# ADC_Board_Right.net
KiCad netlist of a schematic drawn in EAGLE
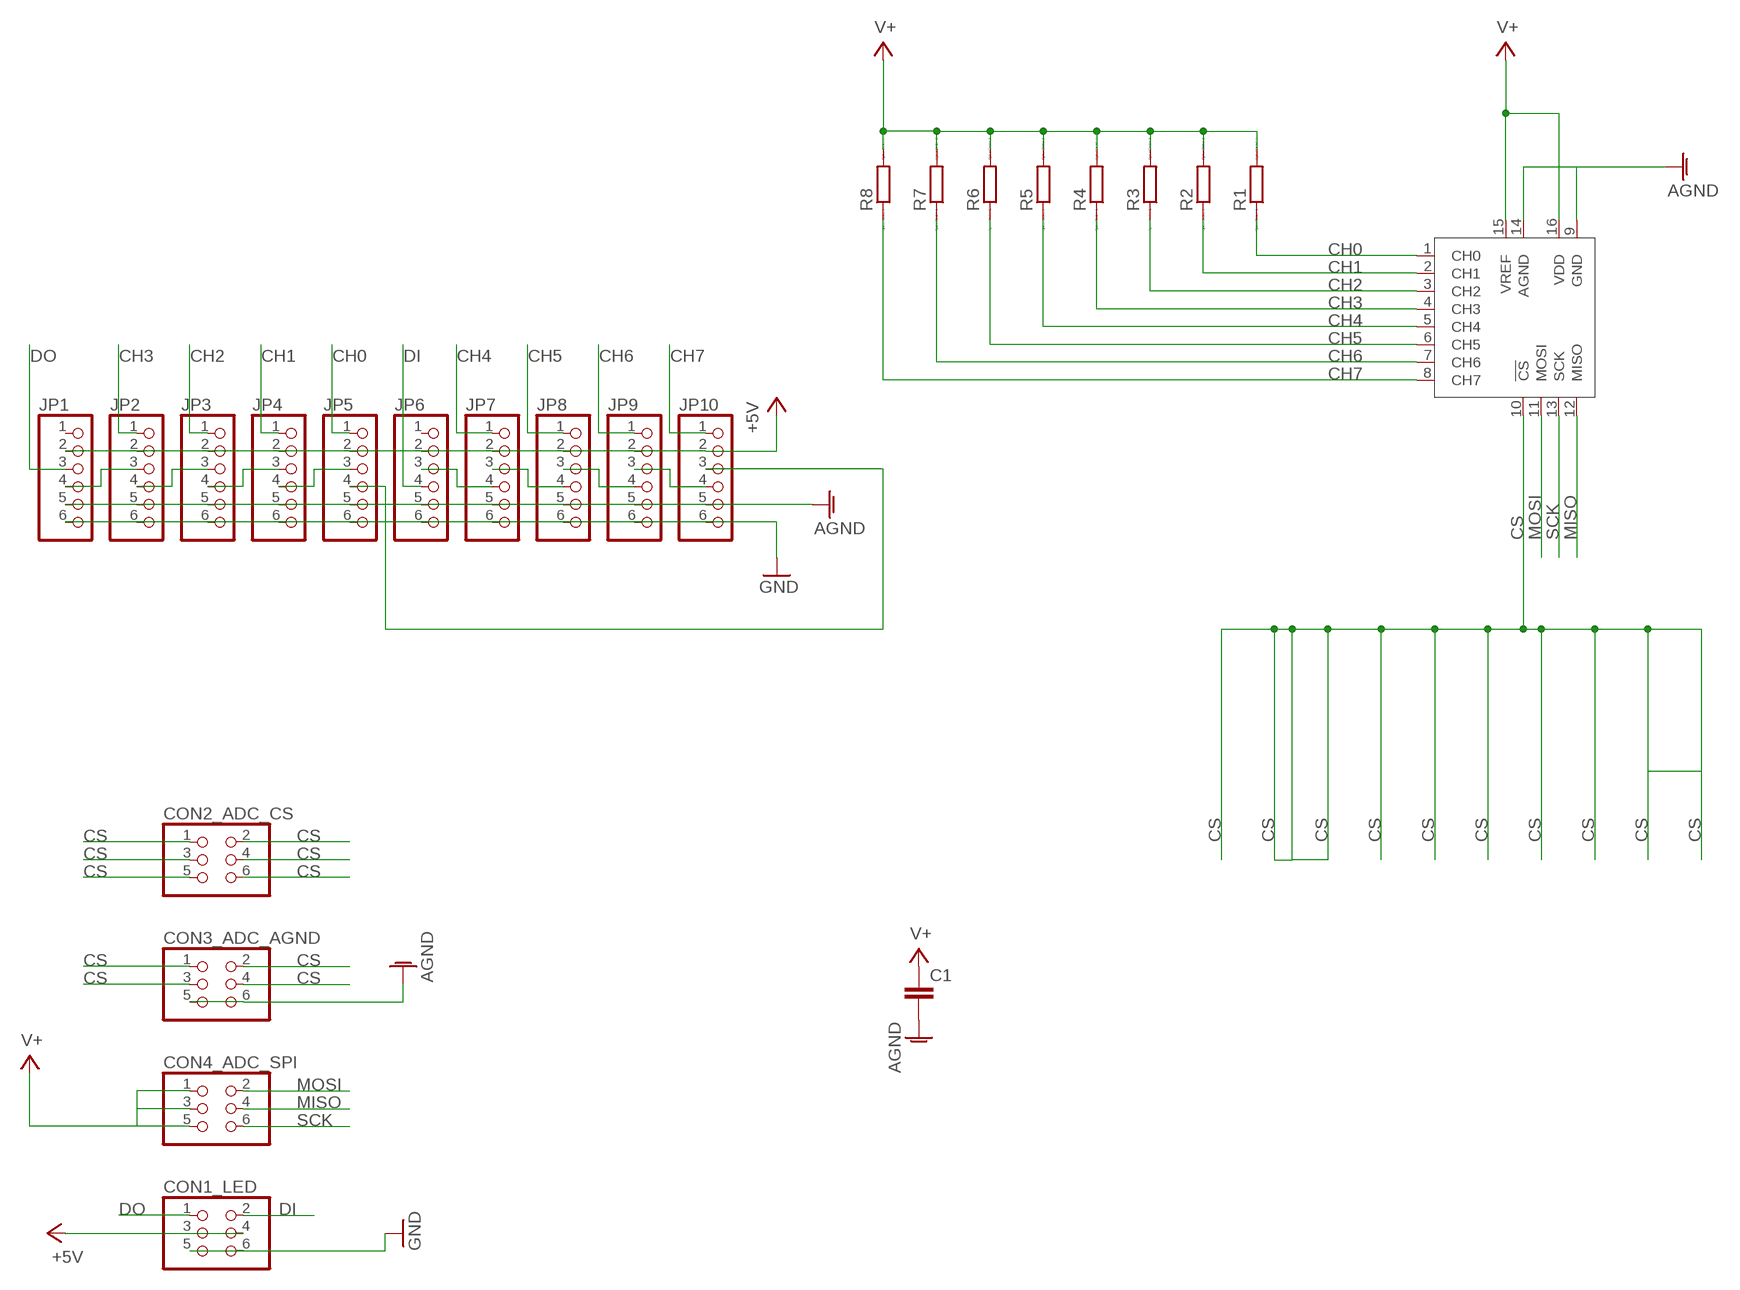
[diagram p0: schematic, sheet 1]

(export (version "E")
  (design (tool "Eeschema 10.0.6"))
  (components
    (comp (ref "C1")
      (value "C-EU050-025X075")
      (footprint "eagle-import:C050-025X075")
      (libsource (lib "eagle-import") (part "C-EU050-025X075"))
    )
    (comp (ref "CON1_LED")
      (value "PINHD-2X3")
      (footprint "eagle-import:2X03")
      (libsource (lib "eagle-import") (part "PINHD-2X3"))
    )
    (comp (ref "CON2_ADC_CS")
      (value "PINHD-2X3")
      (footprint "eagle-import:2X03")
      (libsource (lib "eagle-import") (part "PINHD-2X3"))
    )
    (comp (ref "CON3_ADC_AGND")
      (value "PINHD-2X3")
      (footprint "eagle-import:2X03")
      (libsource (lib "eagle-import") (part "PINHD-2X3"))
    )
    (comp (ref "CON4_ADC_SPI")
      (value "PINHD-2X3")
      (footprint "eagle-import:2X03")
      (libsource (lib "eagle-import") (part "PINHD-2X3"))
    )
    (comp (ref "JP1")
      (value "PINHD-1X6")
      (footprint "eagle-import:1X06")
      (libsource (lib "eagle-import") (part "PINHD-1X6"))
    )
    (comp (ref "JP2")
      (value "PINHD-1X6")
      (footprint "eagle-import:1X06")
      (libsource (lib "eagle-import") (part "PINHD-1X6"))
    )
    (comp (ref "JP3")
      (value "PINHD-1X6")
      (footprint "eagle-import:1X06")
      (libsource (lib "eagle-import") (part "PINHD-1X6"))
    )
    (comp (ref "JP4")
      (value "PINHD-1X6")
      (footprint "eagle-import:1X06")
      (libsource (lib "eagle-import") (part "PINHD-1X6"))
    )
    (comp (ref "JP5")
      (value "PINHD-1X6")
      (footprint "eagle-import:1X06")
      (libsource (lib "eagle-import") (part "PINHD-1X6"))
    )
    (comp (ref "JP6")
      (value "PINHD-1X6")
      (footprint "eagle-import:1X06")
      (libsource (lib "eagle-import") (part "PINHD-1X6"))
    )
    (comp (ref "JP7")
      (value "PINHD-1X6")
      (footprint "eagle-import:1X06")
      (libsource (lib "eagle-import") (part "PINHD-1X6"))
    )
    (comp (ref "JP8")
      (value "PINHD-1X6")
      (footprint "eagle-import:1X06")
      (libsource (lib "eagle-import") (part "PINHD-1X6"))
    )
    (comp (ref "JP9")
      (value "PINHD-1X6")
      (footprint "eagle-import:1X06")
      (libsource (lib "eagle-import") (part "PINHD-1X6"))
    )
    (comp (ref "JP10")
      (value "PINHD-1X6")
      (footprint "eagle-import:1X06")
      (libsource (lib "eagle-import") (part "PINHD-1X6"))
    )
    (comp (ref "R1")
      (value "R-EU_0617_22")
      (footprint "eagle-import:0617_22")
      (libsource (lib "eagle-import") (part "R-EU_0617_22"))
    )
    (comp (ref "R2")
      (value "R-EU_0617_22")
      (footprint "eagle-import:0617_22")
      (libsource (lib "eagle-import") (part "R-EU_0617_22"))
    )
    (comp (ref "R3")
      (value "R-EU_0617_22")
      (footprint "eagle-import:0617_22")
      (libsource (lib "eagle-import") (part "R-EU_0617_22"))
    )
    (comp (ref "R4")
      (value "R-EU_0617_22")
      (footprint "eagle-import:0617_22")
      (libsource (lib "eagle-import") (part "R-EU_0617_22"))
    )
    (comp (ref "R5")
      (value "R-EU_0617_22")
      (footprint "eagle-import:0617_22")
      (libsource (lib "eagle-import") (part "R-EU_0617_22"))
    )
    (comp (ref "R6")
      (value "R-EU_0617_22")
      (footprint "eagle-import:0617_22")
      (libsource (lib "eagle-import") (part "R-EU_0617_22"))
    )
    (comp (ref "R7")
      (value "R-EU_0617_22")
      (footprint "eagle-import:0617_22")
      (libsource (lib "eagle-import") (part "R-EU_0617_22"))
    )
    (comp (ref "R8")
      (value "R-EU_0617_22")
      (footprint "eagle-import:0617_22")
      (libsource (lib "eagle-import") (part "R-EU_0617_22"))
    )
    (comp (ref "U$1")
      (value "MCP3008P")
      (footprint "eagle-import:DIL16")
      (libsource (lib "eagle-import") (part "MCP3008P"))
    )
  )
  (nets
    (net (code "1") (name "+5V") (class "Default")
      (node (ref "CON1_LED") (pin "3") (pinfunction "3_3") (pintype "passive"))
      (node (ref "CON1_LED") (pin "4") (pinfunction "4_4") (pintype "passive"))
      (node (ref "JP1") (pin "2") (pinfunction "2_2") (pintype "passive"))
      (node (ref "JP10") (pin "2") (pinfunction "2_2") (pintype "passive"))
      (node (ref "JP2") (pin "2") (pinfunction "2_2") (pintype "passive"))
      (node (ref "JP3") (pin "2") (pinfunction "2_2") (pintype "passive"))
      (node (ref "JP4") (pin "2") (pinfunction "2_2") (pintype "passive"))
      (node (ref "JP5") (pin "2") (pinfunction "2_2") (pintype "passive"))
      (node (ref "JP6") (pin "2") (pinfunction "2_2") (pintype "passive"))
      (node (ref "JP7") (pin "2") (pinfunction "2_2") (pintype "passive"))
      (node (ref "JP8") (pin "2") (pinfunction "2_2") (pintype "passive"))
      (node (ref "JP9") (pin "2") (pinfunction "2_2") (pintype "passive"))
    )
    (net (code "2") (name "/CH0") (class "Default")
      (node (ref "JP5") (pin "1") (pinfunction "1_1") (pintype "passive"))
      (node (ref "R1") (pin "1") (pinfunction "1_1") (pintype "passive"))
      (node (ref "U$1") (pin "1") (pinfunction "CH0_1") (pintype "input"))
    )
    (net (code "3") (name "/CH1") (class "Default")
      (node (ref "JP4") (pin "1") (pinfunction "1_1") (pintype "passive"))
      (node (ref "R2") (pin "1") (pinfunction "1_1") (pintype "passive"))
      (node (ref "U$1") (pin "2") (pinfunction "CH1_2") (pintype "input"))
    )
    (net (code "4") (name "/CH2") (class "Default")
      (node (ref "JP3") (pin "1") (pinfunction "1_1") (pintype "passive"))
      (node (ref "R3") (pin "1") (pinfunction "1_1") (pintype "passive"))
      (node (ref "U$1") (pin "3") (pinfunction "CH2_3") (pintype "input"))
    )
    (net (code "5") (name "/CH3") (class "Default")
      (node (ref "JP2") (pin "1") (pinfunction "1_1") (pintype "passive"))
      (node (ref "R4") (pin "1") (pinfunction "1_1") (pintype "passive"))
      (node (ref "U$1") (pin "4") (pinfunction "CH3_4") (pintype "input"))
    )
    (net (code "6") (name "/CH4") (class "Default")
      (node (ref "JP7") (pin "1") (pinfunction "1_1") (pintype "passive"))
      (node (ref "R5") (pin "1") (pinfunction "1_1") (pintype "passive"))
      (node (ref "U$1") (pin "5") (pinfunction "CH4_5") (pintype "input"))
    )
    (net (code "7") (name "/CH5") (class "Default")
      (node (ref "JP8") (pin "1") (pinfunction "1_1") (pintype "passive"))
      (node (ref "R6") (pin "1") (pinfunction "1_1") (pintype "passive"))
      (node (ref "U$1") (pin "6") (pinfunction "CH5_6") (pintype "input"))
    )
    (net (code "8") (name "/CH6") (class "Default")
      (node (ref "JP9") (pin "1") (pinfunction "1_1") (pintype "passive"))
      (node (ref "R7") (pin "1") (pinfunction "1_1") (pintype "passive"))
      (node (ref "U$1") (pin "7") (pinfunction "CH6_7") (pintype "input"))
    )
    (net (code "9") (name "/CH7") (class "Default")
      (node (ref "JP10") (pin "1") (pinfunction "1_1") (pintype "passive"))
      (node (ref "R8") (pin "1") (pinfunction "1_1") (pintype "passive"))
      (node (ref "U$1") (pin "8") (pinfunction "CH7_8") (pintype "input"))
    )
    (net (code "10") (name "/CS") (class "Default")
      (node (ref "CON2_ADC_CS") (pin "1") (pinfunction "1_1") (pintype "passive"))
      (node (ref "CON2_ADC_CS") (pin "2") (pinfunction "2_2") (pintype "passive"))
      (node (ref "CON2_ADC_CS") (pin "3") (pinfunction "3_3") (pintype "passive"))
      (node (ref "CON2_ADC_CS") (pin "4") (pinfunction "4_4") (pintype "passive"))
      (node (ref "CON2_ADC_CS") (pin "5") (pinfunction "5_5") (pintype "passive"))
      (node (ref "CON2_ADC_CS") (pin "6") (pinfunction "6_6") (pintype "passive"))
      (node (ref "CON3_ADC_AGND") (pin "1") (pinfunction "1_1") (pintype "passive"))
      (node (ref "CON3_ADC_AGND") (pin "2") (pinfunction "2_2") (pintype "passive"))
      (node (ref "CON3_ADC_AGND") (pin "3") (pinfunction "3_3") (pintype "passive"))
      (node (ref "CON3_ADC_AGND") (pin "4") (pinfunction "4_4") (pintype "passive"))
      (node (ref "U$1") (pin "10") (pinfunction "~{CS}_10") (pintype "input"))
    )
    (net (code "11") (name "/DI") (class "Default")
      (node (ref "CON1_LED") (pin "2") (pinfunction "2_2") (pintype "passive"))
      (node (ref "JP6") (pin "4") (pinfunction "4_4") (pintype "passive"))
    )
    (net (code "12") (name "/DO") (class "Default")
      (node (ref "CON1_LED") (pin "1") (pinfunction "1_1") (pintype "passive"))
      (node (ref "JP1") (pin "3") (pinfunction "3_3") (pintype "passive"))
    )
    (net (code "13") (name "/MISO") (class "Default")
      (node (ref "CON4_ADC_SPI") (pin "4") (pinfunction "4_4") (pintype "passive"))
      (node (ref "U$1") (pin "12") (pinfunction "MISO_12") (pintype "output"))
    )
    (net (code "14") (name "/MOSI") (class "Default")
      (node (ref "CON4_ADC_SPI") (pin "2") (pinfunction "2_2") (pintype "passive"))
      (node (ref "U$1") (pin "11") (pinfunction "MOSI_11") (pintype "input"))
    )
    (net (code "15") (name "/SCK") (class "Default")
      (node (ref "CON4_ADC_SPI") (pin "6") (pinfunction "6_6") (pintype "passive"))
      (node (ref "U$1") (pin "13") (pinfunction "SCK_13") (pintype "input"))
    )
    (net (code "16") (name "AGND") (class "Default")
      (node (ref "C1") (pin "2") (pinfunction "2_2") (pintype "passive"))
      (node (ref "CON3_ADC_AGND") (pin "5") (pinfunction "5_5") (pintype "passive"))
      (node (ref "CON3_ADC_AGND") (pin "6") (pinfunction "6_6") (pintype "passive"))
      (node (ref "JP1") (pin "5") (pinfunction "5_5") (pintype "passive"))
      (node (ref "JP10") (pin "5") (pinfunction "5_5") (pintype "passive"))
      (node (ref "JP2") (pin "5") (pinfunction "5_5") (pintype "passive"))
      (node (ref "JP3") (pin "5") (pinfunction "5_5") (pintype "passive"))
      (node (ref "JP4") (pin "5") (pinfunction "5_5") (pintype "passive"))
      (node (ref "JP5") (pin "5") (pinfunction "5_5") (pintype "passive"))
      (node (ref "JP6") (pin "5") (pinfunction "5_5") (pintype "passive"))
      (node (ref "JP7") (pin "5") (pinfunction "5_5") (pintype "passive"))
      (node (ref "JP8") (pin "5") (pinfunction "5_5") (pintype "passive"))
      (node (ref "JP9") (pin "5") (pinfunction "5_5") (pintype "passive"))
      (node (ref "U$1") (pin "14") (pinfunction "AGND_14") (pintype "power_in"))
      (node (ref "U$1") (pin "9") (pinfunction "GND_9") (pintype "power_in"))
    )
    (net (code "17") (name "GND") (class "Default")
      (node (ref "CON1_LED") (pin "5") (pinfunction "5_5") (pintype "passive"))
      (node (ref "CON1_LED") (pin "6") (pinfunction "6_6") (pintype "passive"))
      (node (ref "JP1") (pin "6") (pinfunction "6_6") (pintype "passive"))
      (node (ref "JP10") (pin "6") (pinfunction "6_6") (pintype "passive"))
      (node (ref "JP2") (pin "6") (pinfunction "6_6") (pintype "passive"))
      (node (ref "JP3") (pin "6") (pinfunction "6_6") (pintype "passive"))
      (node (ref "JP4") (pin "6") (pinfunction "6_6") (pintype "passive"))
      (node (ref "JP5") (pin "6") (pinfunction "6_6") (pintype "passive"))
      (node (ref "JP6") (pin "6") (pinfunction "6_6") (pintype "passive"))
      (node (ref "JP7") (pin "6") (pinfunction "6_6") (pintype "passive"))
      (node (ref "JP8") (pin "6") (pinfunction "6_6") (pintype "passive"))
      (node (ref "JP9") (pin "6") (pinfunction "6_6") (pintype "passive"))
    )
    (net (code "18") (name "Net-(JP1-Pad4)") (class "Default")
      (node (ref "JP1") (pin "4") (pinfunction "4_4") (pintype "passive"))
      (node (ref "JP2") (pin "3") (pinfunction "3_3") (pintype "passive"))
    )
    (net (code "19") (name "Net-(JP2-Pad4)") (class "Default")
      (node (ref "JP2") (pin "4") (pinfunction "4_4") (pintype "passive"))
      (node (ref "JP3") (pin "3") (pinfunction "3_3") (pintype "passive"))
    )
    (net (code "20") (name "Net-(JP3-Pad4)") (class "Default")
      (node (ref "JP3") (pin "4") (pinfunction "4_4") (pintype "passive"))
      (node (ref "JP4") (pin "3") (pinfunction "3_3") (pintype "passive"))
    )
    (net (code "21") (name "Net-(JP4-Pad4)") (class "Default")
      (node (ref "JP4") (pin "4") (pinfunction "4_4") (pintype "passive"))
      (node (ref "JP5") (pin "3") (pinfunction "3_3") (pintype "passive"))
    )
    (net (code "22") (name "Net-(JP6-Pad3)") (class "Default")
      (node (ref "JP6") (pin "3") (pinfunction "3_3") (pintype "passive"))
      (node (ref "JP7") (pin "4") (pinfunction "4_4") (pintype "passive"))
    )
    (net (code "23") (name "Net-(JP7-Pad3)") (class "Default")
      (node (ref "JP7") (pin "3") (pinfunction "3_3") (pintype "passive"))
      (node (ref "JP8") (pin "4") (pinfunction "4_4") (pintype "passive"))
    )
    (net (code "24") (name "Net-(JP8-Pad3)") (class "Default")
      (node (ref "JP8") (pin "3") (pinfunction "3_3") (pintype "passive"))
      (node (ref "JP9") (pin "4") (pinfunction "4_4") (pintype "passive"))
    )
    (net (code "25") (name "Net-(JP10-Pad3)") (class "Default")
      (node (ref "JP10") (pin "3") (pinfunction "3_3") (pintype "passive"))
      (node (ref "JP5") (pin "4") (pinfunction "4_4") (pintype "passive"))
    )
    (net (code "26") (name "Net-(JP10-Pad4)") (class "Default")
      (node (ref "JP10") (pin "4") (pinfunction "4_4") (pintype "passive"))
      (node (ref "JP9") (pin "3") (pinfunction "3_3") (pintype "passive"))
    )
    (net (code "27") (name "V+") (class "Default")
      (node (ref "C1") (pin "1") (pinfunction "1_1") (pintype "passive"))
      (node (ref "CON4_ADC_SPI") (pin "1") (pinfunction "1_1") (pintype "passive"))
      (node (ref "CON4_ADC_SPI") (pin "3") (pinfunction "3_3") (pintype "passive"))
      (node (ref "CON4_ADC_SPI") (pin "5") (pinfunction "5_5") (pintype "passive"))
      (node (ref "R1") (pin "2") (pinfunction "2_2") (pintype "passive"))
      (node (ref "R2") (pin "2") (pinfunction "2_2") (pintype "passive"))
      (node (ref "R3") (pin "2") (pinfunction "2_2") (pintype "passive"))
      (node (ref "R4") (pin "2") (pinfunction "2_2") (pintype "passive"))
      (node (ref "R5") (pin "2") (pinfunction "2_2") (pintype "passive"))
      (node (ref "R6") (pin "2") (pinfunction "2_2") (pintype "passive"))
      (node (ref "R7") (pin "2") (pinfunction "2_2") (pintype "passive"))
      (node (ref "R8") (pin "2") (pinfunction "2_2") (pintype "passive"))
      (node (ref "U$1") (pin "15") (pinfunction "VREF_15") (pintype "power_in"))
      (node (ref "U$1") (pin "16") (pinfunction "VDD_16") (pintype "power_in"))
    )
    (net (code "28") (name "unconnected-(JP1-Pad1)") (class "Default")
      (node (ref "JP1") (pin "1") (pinfunction "1_1") (pintype "passive"))
    )
    (net (code "29") (name "unconnected-(JP6-Pad1)") (class "Default")
      (node (ref "JP6") (pin "1") (pinfunction "1_1") (pintype "passive"))
    )
  )
)
